# Connector_A.net
KiCad netlist of a schematic drawn in Altium Designer
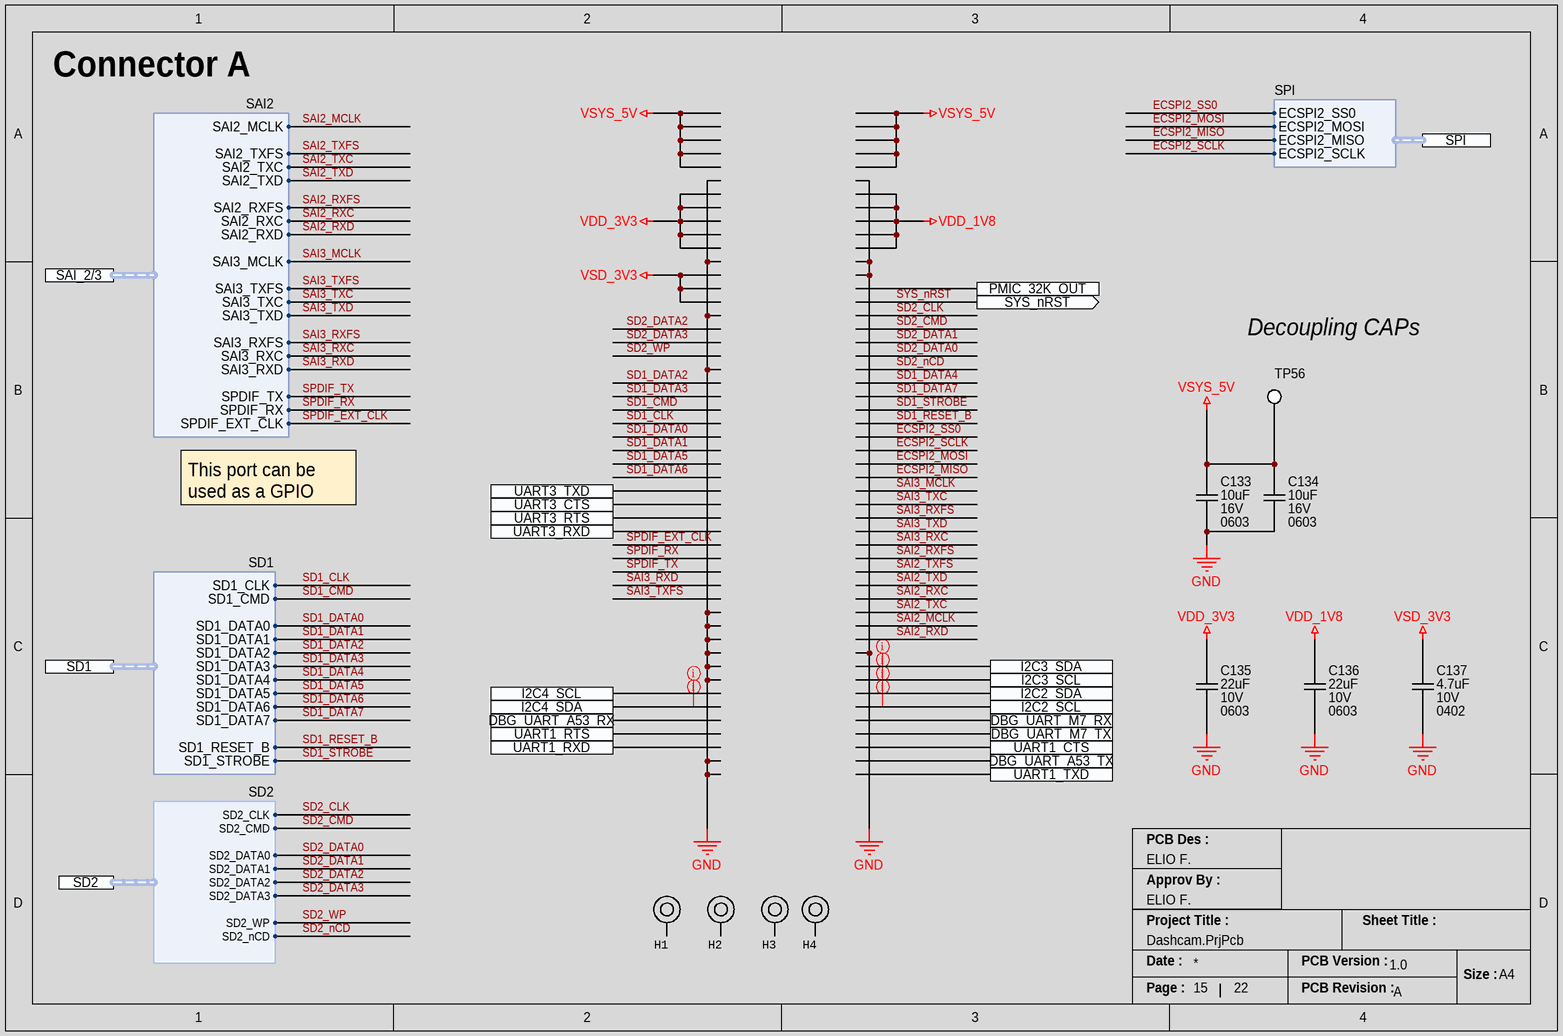
[diagram p0: Connector A.SchDoc]

(export (version "E")
  (design (tool "Eeschema 10.0.6"))
  (components
    (comp (ref "C133")
      (value "GRM188R61C106MAALD")
      (footprint "CAP_0603_CAPC1608X08N")
      (description "0603 10 uF 16 V ±20% Tolerance X5R Multilayer Ceramic Chip Capacitor")
      (fields
        (field (name "MANUFACTURER") "Murata")
        (field (name "TOLERANCE") "20%")
        (field (name "VOLTAGE RATING") "16V")
        (field (name "CAPACITANCE") "10uF")
        (field (name "CASE/PACKAGE") "0603")
      )
      (libsource (lib "Electronic Devices_LIB") (part "CAP_10UF_16V_X5R_0603"))
    )
    (comp (ref "C134")
      (value "GRM188R61C106MAALD")
      (footprint "CAP_0603_CAPC1608X08N")
      (description "0603 10 uF 16 V ±20% Tolerance X5R Multilayer Ceramic Chip Capacitor")
      (fields
        (field (name "MANUFACTURER") "Murata")
        (field (name "TOLERANCE") "20%")
        (field (name "VOLTAGE RATING") "16V")
        (field (name "CAPACITANCE") "10uF")
        (field (name "CASE/PACKAGE") "0603")
      )
      (libsource (lib "Electronic Devices_LIB") (part "CAP_10UF_16V_X5R_0603"))
    )
    (comp (ref "C135")
      (value "C1608X5R1A226M080AC")
      (footprint "CAP_0603_CAPC1608X08N")
      (description "Multilayer Ceramic Capacitor, 22 uF, 10 V, ± 20%, X5R, 0603 [1608 Metric]")
      (fields
        (field (name "MANUFACTURER") "TDK")
        (field (name "TOLERANCE") "20%")
        (field (name "CAPACITANCE") "22uF")
        (field (name "VOLTAGE RATING") "10V")
        (field (name "CASE CODE (IMPERIAL)") "0603")
      )
      (libsource (lib "Electronic Devices_LIB") (part "CAP_22UF_10V_X5R_0603"))
    )
    (comp (ref "C136")
      (value "C1608X5R1A226M080AC")
      (footprint "CAP_0603_CAPC1608X08N")
      (description "Multilayer Ceramic Capacitor, 22 uF, 10 V, ± 20%, X5R, 0603 [1608 Metric]")
      (fields
        (field (name "MANUFACTURER") "TDK")
        (field (name "TOLERANCE") "20%")
        (field (name "CAPACITANCE") "22uF")
        (field (name "VOLTAGE RATING") "10V")
        (field (name "CASE CODE (IMPERIAL)") "0603")
      )
      (libsource (lib "Electronic Devices_LIB") (part "CAP_22UF_10V_X5R_0603"))
    )
    (comp (ref "C137")
      (value "CL05A475KP5NRNC")
      (footprint "CAP_0402_CAPC1005X05N")
      (description "Multilayer Ceramic Capacitor, 4.7 uF, 10 V, ± 10%, X5R, 0402 [1005 Metric]")
      (fields
        (field (name "MANUFACTURER") "Samsung")
        (field (name "TOLERANCE") "10%")
        (field (name "CAPACITANCE") "4.7uF")
        (field (name "VOLTAGE RATING") "10V")
        (field (name "CASE/PACKAGE") "0402")
      )
      (libsource (lib "Electronic Devices_LIB") (part "CAP_4.7UF_10V_X5R_0402"))
    )
    (comp (ref "H1")
      (value "Mounting Hole")
      (footprint "PTH_3.2X5")
      (description "Mounting Hole, Plated")
      (libsource (lib "Electronic Devices_LIB") (part "MECHANICALS_MOUNT_PTH"))
    )
    (comp (ref "H2")
      (value "Mounting Hole")
      (footprint "PTH_3.2X5")
      (description "Mounting Hole, Plated")
      (libsource (lib "Electronic Devices_LIB") (part "MECHANICALS_MOUNT_PTH"))
    )
    (comp (ref "H3")
      (value "Mounting Hole")
      (footprint "PTH_3.2X5")
      (description "Mounting Hole, Plated")
      (libsource (lib "Electronic Devices_LIB") (part "MECHANICALS_MOUNT_PTH"))
    )
    (comp (ref "H4")
      (value "Mounting Hole")
      (footprint "PTH_3.2X5")
      (description "Mounting Hole, Plated")
      (libsource (lib "Electronic Devices_LIB") (part "MECHANICALS_MOUNT_PTH"))
    )
    (comp (ref "TP56")
      (value "NO COMPONENT")
      (footprint "TP_PAD_0.8MM_SMD_ROUND")
      (description "Test Point, SMD pad, round, 1.5mm, 1.6mm, 3mm diameter")
      (libsource (lib "Electronic Devices_LIB") (part "TP_PAD_SMD_Round"))
    )
  )
  (nets
    (net (code "70") (name "GND") (class "Default")
      (node (ref "C133") (pin "1") (pinfunction "1_1") (pintype "passive"))
      (node (ref "C134") (pin "1") (pinfunction "1_1") (pintype "passive"))
      (node (ref "C135") (pin "1") (pinfunction "1_1") (pintype "passive"))
      (node (ref "C136") (pin "1") (pinfunction "1_1") (pintype "passive"))
      (node (ref "C137") (pin "1") (pinfunction "1_1") (pintype "passive"))
    )
    (net (code "71") (name "VDD_1V8") (class "Default")
      (node (ref "C136") (pin "2") (pinfunction "2_2") (pintype "passive"))
    )
    (net (code "72") (name "VDD_3V3") (class "Default")
      (node (ref "C135") (pin "2") (pinfunction "2_2") (pintype "passive"))
    )
    (net (code "73") (name "VSD_3V3") (class "Default")
      (node (ref "C137") (pin "2") (pinfunction "2_2") (pintype "passive"))
    )
    (net (code "74") (name "VSYS_5V") (class "Default")
      (node (ref "C133") (pin "2") (pinfunction "2_2") (pintype "passive"))
      (node (ref "C134") (pin "2") (pinfunction "2_2") (pintype "passive"))
      (node (ref "TP56") (pin "1") (pinfunction "1_1") (pintype "passive"))
    )
    (net (code "75") (name "unconnected-(H1-Pad1)") (class "Default")
      (node (ref "H1") (pin "1") (pinfunction "1_1") (pintype "passive"))
    )
    (net (code "76") (name "unconnected-(H2-Pad1)") (class "Default")
      (node (ref "H2") (pin "1") (pinfunction "1_1") (pintype "passive"))
    )
    (net (code "77") (name "unconnected-(H3-Pad1)") (class "Default")
      (node (ref "H3") (pin "1") (pinfunction "1_1") (pintype "passive"))
    )
    (net (code "78") (name "unconnected-(H4-Pad1)") (class "Default")
      (node (ref "H4") (pin "1") (pinfunction "1_1") (pintype "passive"))
    )
  )
)
